# AX12hat.net
KiCad netlist of a schematic drawn in EAGLE
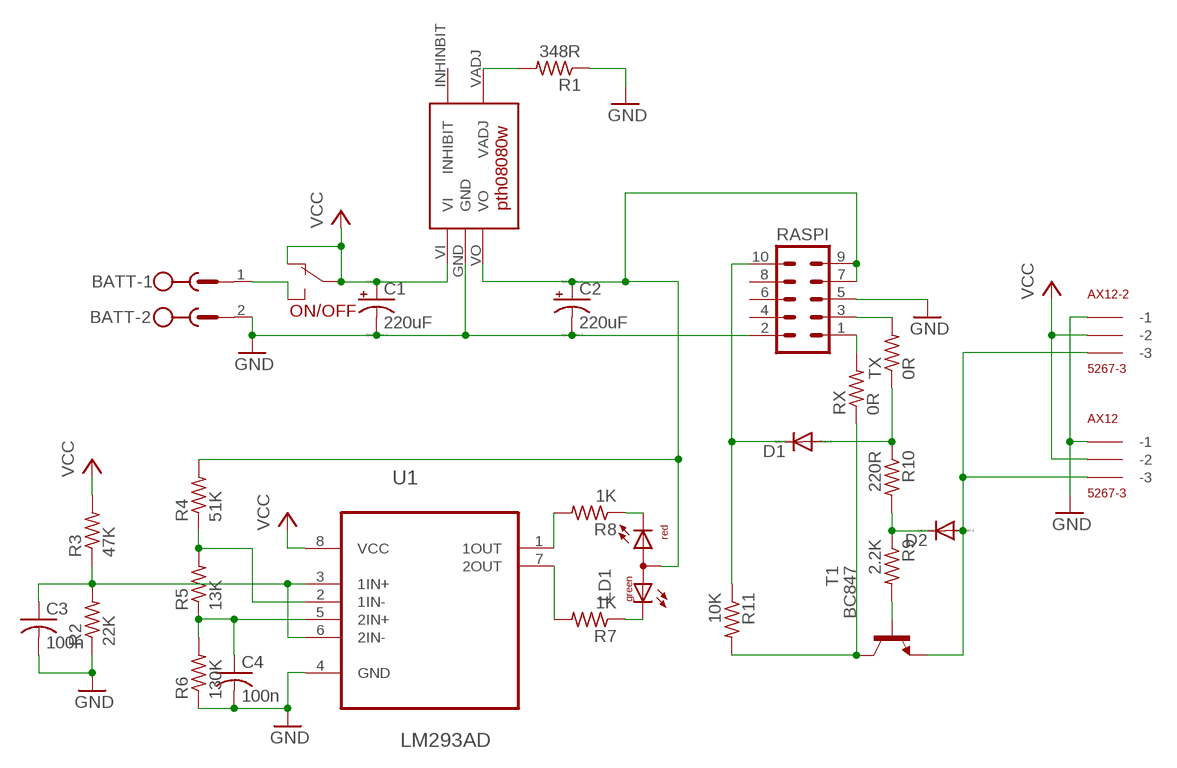
[diagram p0: schematic, sheet 1]

(export (version "E")
  (design (tool "Eeschema 10.0.6"))
  (components
    (comp (ref "AX12")
      (value "5267-3")
      (footprint "eagle-import:5267-3")
      (libsource (lib "eagle-import") (part "5267-3"))
    )
    (comp (ref "AX12-2")
      (value "5267-3")
      (footprint "eagle-import:5267-3")
      (libsource (lib "eagle-import") (part "5267-3"))
    )
    (comp (ref "BATT")
      (value "MSTBV2")
      (footprint "eagle-import:MSTBV2")
      (libsource (lib "eagle-import") (part "MSTBV2"))
    )
    (comp (ref "C1")
      (value "220uF")
      (footprint "eagle-import:E2,5-7")
      (libsource (lib "eagle-import") (part "CPOL-USE2.5-7"))
    )
    (comp (ref "C2")
      (value "220uF")
      (footprint "eagle-import:E2,5-7")
      (libsource (lib "eagle-import") (part "CPOL-USE2.5-7"))
    )
    (comp (ref "C3")
      (value "100n")
      (footprint "eagle-import:C0805")
      (libsource (lib "eagle-import") (part "C-USC0805"))
    )
    (comp (ref "C4")
      (value "100n")
      (footprint "eagle-import:C0805")
      (libsource (lib "eagle-import") (part "C-USC0805"))
    )
    (comp (ref "D1")
      (value "DIODE-SOD523")
      (footprint "eagle-import:SOD523")
      (libsource (lib "eagle-import") (part "DIODE-SOD523"))
    )
    (comp (ref "D2")
      (value "DIODE-SOD523")
      (footprint "eagle-import:SOD523")
      (libsource (lib "eagle-import") (part "DIODE-SOD523"))
    )
    (comp (ref "LD1")
      (value "DUOLED-RG-A")
      (footprint "eagle-import:DUOLED-A-5MM")
      (libsource (lib "eagle-import") (part "DUOLED-RG-A"))
    )
    (comp (ref "ON/OFF")
      (value "SWITCH")
      (footprint "eagle-import:SWITCH")
      (libsource (lib "eagle-import") (part "SWITCH"))
    )
    (comp (ref "R1")
      (value "348R")
      (footprint "eagle-import:R0805")
      (libsource (lib "eagle-import") (part "R-US_R0805"))
    )
    (comp (ref "R2")
      (value "22K")
      (footprint "eagle-import:R0805")
      (libsource (lib "eagle-import") (part "R-US_R0805"))
    )
    (comp (ref "R3")
      (value "47K")
      (footprint "eagle-import:R0805")
      (libsource (lib "eagle-import") (part "R-US_R0805"))
    )
    (comp (ref "R4")
      (value "51K")
      (footprint "eagle-import:R0805")
      (libsource (lib "eagle-import") (part "R-US_R0805"))
    )
    (comp (ref "R5")
      (value "13K")
      (footprint "eagle-import:R0805")
      (libsource (lib "eagle-import") (part "R-US_R0805"))
    )
    (comp (ref "R6")
      (value "130K")
      (footprint "eagle-import:R0805")
      (libsource (lib "eagle-import") (part "R-US_R0805"))
    )
    (comp (ref "R7")
      (value "1K")
      (footprint "eagle-import:R0805")
      (libsource (lib "eagle-import") (part "R-US_R0805"))
    )
    (comp (ref "R8")
      (value "1K")
      (footprint "eagle-import:R0805")
      (libsource (lib "eagle-import") (part "R-US_R0805"))
    )
    (comp (ref "R9")
      (value "2.2K")
      (footprint "eagle-import:R0805")
      (libsource (lib "eagle-import") (part "R-US_R0805"))
    )
    (comp (ref "R10")
      (value "220R")
      (footprint "eagle-import:R0805")
      (libsource (lib "eagle-import") (part "R-US_R0805"))
    )
    (comp (ref "R11")
      (value "10K")
      (footprint "eagle-import:R0805")
      (libsource (lib "eagle-import") (part "R-US_R0805"))
    )
    (comp (ref "RASPI")
      (value "MA05-2")
      (footprint "eagle-import:MA05-2")
      (libsource (lib "eagle-import") (part "MA05-2"))
    )
    (comp (ref "RX")
      (value "0R")
      (footprint "eagle-import:R0805")
      (libsource (lib "eagle-import") (part "R-US_R0805"))
    )
    (comp (ref "T1")
      (value "BC847")
      (footprint "eagle-import:SOT23")
      (libsource (lib "eagle-import") (part "BC847"))
    )
    (comp (ref "TX")
      (value "0R")
      (footprint "eagle-import:R0805")
      (libsource (lib "eagle-import") (part "R-US_R0805"))
    )
    (comp (ref "U$1")
      (value "REGUL_PTH")
      (footprint "eagle-import:REGUL_PTH")
      (libsource (lib "eagle-import") (part "REGUL_PTH"))
    )
    (comp (ref "U1")
      (value "LM293AD")
      (footprint "eagle-import:SOIC127P600X175-8N")
      (libsource (lib "eagle-import") (part "LM293AD"))
    )
  )
  (nets
    (net (code "1") (name "GND") (class "Default")
      (node (ref "AX12") (pin "P$1") (pinfunction "-1_P$1") (pintype "bidirectional"))
      (node (ref "AX12-2") (pin "P$1") (pinfunction "-1_P$1") (pintype "bidirectional"))
      (node (ref "BATT") (pin "2") (pinfunction "SK_2") (pintype "passive"))
      (node (ref "C1") (pin "-") (pinfunction "-_-") (pintype "passive"))
      (node (ref "C2") (pin "-") (pinfunction "-_-") (pintype "passive"))
      (node (ref "C3") (pin "2") (pinfunction "2_2") (pintype "passive"))
      (node (ref "C4") (pin "2") (pinfunction "2_2") (pintype "passive"))
      (node (ref "R1") (pin "1") (pinfunction "1_1") (pintype "passive"))
      (node (ref "R2") (pin "1") (pinfunction "1_1") (pintype "passive"))
      (node (ref "R6") (pin "1") (pinfunction "1_1") (pintype "passive"))
      (node (ref "RASPI") (pin "2") (pinfunction "2_2") (pintype "passive"))
      (node (ref "RASPI") (pin "5") (pinfunction "5_5") (pintype "passive"))
      (node (ref "U$1") (pin "GND") (pinfunction "GND_GND") (pintype "bidirectional"))
      (node (ref "U1") (pin "4") (pinfunction "GND_4") (pintype "passive"))
    )
    (net (code "2") (name "Net-(AX12--3)") (class "Default")
      (node (ref "AX12") (pin "P$3") (pinfunction "-3_P$3") (pintype "bidirectional"))
      (node (ref "AX12-2") (pin "P$3") (pinfunction "-3_P$3") (pintype "bidirectional"))
      (node (ref "D2") (pin "A") (pinfunction "A_A") (pintype "passive"))
      (node (ref "T1") (pin "2") (pinfunction "E_2") (pintype "passive"))
    )
    (net (code "3") (name "Net-(BATTA-SK)") (class "Default")
      (node (ref "BATT") (pin "1") (pinfunction "SK_1") (pintype "passive"))
      (node (ref "ON/OFF") (pin "P$3") (pinfunction "3_P$3") (pintype "bidirectional"))
    )
    (net (code "4") (name "Net-(C2-Pad+)") (class "Default")
      (node (ref "C2") (pin "+") (pinfunction "+_+") (pintype "passive"))
      (node (ref "LD1") (pin "A") (pinfunction "A_A") (pintype "passive"))
      (node (ref "R4") (pin "2") (pinfunction "2_2") (pintype "passive"))
      (node (ref "RASPI") (pin "7") (pinfunction "7_7") (pintype "passive"))
      (node (ref "RASPI") (pin "9") (pinfunction "9_9") (pintype "passive"))
      (node (ref "U$1") (pin "VO") (pinfunction "VO_VO") (pintype "bidirectional"))
    )
    (net (code "5") (name "Net-(D1-PadA)") (class "Default")
      (node (ref "D1") (pin "A") (pinfunction "A_A") (pintype "passive"))
      (node (ref "R10") (pin "1") (pinfunction "1_1") (pintype "passive"))
      (node (ref "TX") (pin "1") (pinfunction "1_1") (pintype "passive"))
    )
    (net (code "6") (name "Net-(D1-PadC)") (class "Default")
      (node (ref "D1") (pin "C") (pinfunction "C_C") (pintype "passive"))
      (node (ref "R11") (pin "1") (pinfunction "1_1") (pintype "passive"))
      (node (ref "RASPI") (pin "10") (pinfunction "10_10") (pintype "passive"))
    )
    (net (code "7") (name "Net-(D2-PadC)") (class "Default")
      (node (ref "D2") (pin "C") (pinfunction "C_C") (pintype "passive"))
      (node (ref "R10") (pin "2") (pinfunction "2_2") (pintype "passive"))
      (node (ref "R9") (pin "1") (pinfunction "1_1") (pintype "passive"))
    )
    (net (code "8") (name "Net-(LD1-CG)") (class "Default")
      (node (ref "LD1") (pin "CX") (pinfunction "CG_CX") (pintype "passive"))
      (node (ref "R7") (pin "1") (pinfunction "1_1") (pintype "passive"))
    )
    (net (code "9") (name "Net-(LD1-PadCR)") (class "Default")
      (node (ref "LD1") (pin "CR") (pinfunction "CR_CR") (pintype "passive"))
      (node (ref "R8") (pin "1") (pinfunction "1_1") (pintype "passive"))
    )
    (net (code "10") (name "Net-(R1-Pad2)") (class "Default")
      (node (ref "R1") (pin "2") (pinfunction "2_2") (pintype "passive"))
      (node (ref "U$1") (pin "VADJ") (pinfunction "VADJ_VADJ") (pintype "bidirectional"))
    )
    (net (code "11") (name "Net-(RASPI-Pad1)") (class "Default")
      (node (ref "RASPI") (pin "1") (pinfunction "1_1") (pintype "passive"))
      (node (ref "RX") (pin "2") (pinfunction "2_2") (pintype "passive"))
    )
    (net (code "12") (name "Net-(RASPI-Pad3)") (class "Default")
      (node (ref "RASPI") (pin "3") (pinfunction "3_3") (pintype "passive"))
      (node (ref "TX") (pin "2") (pinfunction "2_2") (pintype "passive"))
    )
    (net (code "13") (name "Net-(T1-B)") (class "Default")
      (node (ref "R9") (pin "2") (pinfunction "2_2") (pintype "passive"))
      (node (ref "T1") (pin "1") (pinfunction "B_1") (pintype "passive"))
    )
    (net (code "14") (name "Net-(T1-C)") (class "Default")
      (node (ref "R11") (pin "2") (pinfunction "2_2") (pintype "passive"))
      (node (ref "RX") (pin "1") (pinfunction "1_1") (pintype "passive"))
      (node (ref "T1") (pin "3") (pinfunction "C_3") (pintype "passive"))
    )
    (net (code "15") (name "Net-(U1-1IN+)") (class "Default")
      (node (ref "C3") (pin "1") (pinfunction "1_1") (pintype "passive"))
      (node (ref "R2") (pin "2") (pinfunction "2_2") (pintype "passive"))
      (node (ref "R3") (pin "1") (pinfunction "1_1") (pintype "passive"))
      (node (ref "U1") (pin "3") (pinfunction "1IN+_3") (pintype "input"))
      (node (ref "U1") (pin "6") (pinfunction "2IN-_6") (pintype "input"))
    )
    (net (code "16") (name "Net-(U1-1IN-)") (class "Default")
      (node (ref "R4") (pin "1") (pinfunction "1_1") (pintype "passive"))
      (node (ref "R5") (pin "2") (pinfunction "2_2") (pintype "passive"))
      (node (ref "U1") (pin "2") (pinfunction "1IN-_2") (pintype "input"))
    )
    (net (code "17") (name "Net-(U1-1OUT)") (class "Default")
      (node (ref "R8") (pin "2") (pinfunction "2_2") (pintype "passive"))
      (node (ref "U1") (pin "1") (pinfunction "1OUT_1") (pintype "output"))
    )
    (net (code "18") (name "Net-(U1-2IN+)") (class "Default")
      (node (ref "C4") (pin "1") (pinfunction "1_1") (pintype "passive"))
      (node (ref "R5") (pin "1") (pinfunction "1_1") (pintype "passive"))
      (node (ref "R6") (pin "2") (pinfunction "2_2") (pintype "passive"))
      (node (ref "U1") (pin "5") (pinfunction "2IN+_5") (pintype "input"))
    )
    (net (code "19") (name "Net-(U1-2OUT)") (class "Default")
      (node (ref "R7") (pin "2") (pinfunction "2_2") (pintype "passive"))
      (node (ref "U1") (pin "7") (pinfunction "2OUT_7") (pintype "output"))
    )
    (net (code "20") (name "VCC") (class "Default")
      (node (ref "AX12") (pin "P$2") (pinfunction "-2_P$2") (pintype "bidirectional"))
      (node (ref "AX12-2") (pin "P$2") (pinfunction "-2_P$2") (pintype "bidirectional"))
      (node (ref "C1") (pin "+") (pinfunction "+_+") (pintype "passive"))
      (node (ref "ON/OFF") (pin "P$1") (pinfunction "1_P$1") (pintype "bidirectional"))
      (node (ref "ON/OFF") (pin "P$2") (pinfunction "2_P$2") (pintype "bidirectional"))
      (node (ref "R3") (pin "2") (pinfunction "2_2") (pintype "passive"))
      (node (ref "U$1") (pin "VI") (pinfunction "VI_VI") (pintype "bidirectional"))
      (node (ref "U1") (pin "8") (pinfunction "VCC_8") (pintype "power_in"))
    )
    (net (code "21") (name "unconnected-(RASPI-Pad4)") (class "Default")
      (node (ref "RASPI") (pin "4") (pinfunction "4_4") (pintype "passive"))
    )
    (net (code "22") (name "unconnected-(RASPI-Pad6)") (class "Default")
      (node (ref "RASPI") (pin "6") (pinfunction "6_6") (pintype "passive"))
    )
    (net (code "23") (name "unconnected-(RASPI-Pad8)") (class "Default")
      (node (ref "RASPI") (pin "8") (pinfunction "8_8") (pintype "passive"))
    )
    (net (code "24") (name "unconnected-(U$1-INHIBIT-PadINHINBIT)") (class "Default")
      (node (ref "U$1") (pin "INHINBIT") (pinfunction "INHIBIT_INHINBIT") (pintype "bidirectional"))
    )
  )
)
